# msgeq7-simple.net
KiCad netlist of a schematic drawn in EAGLE
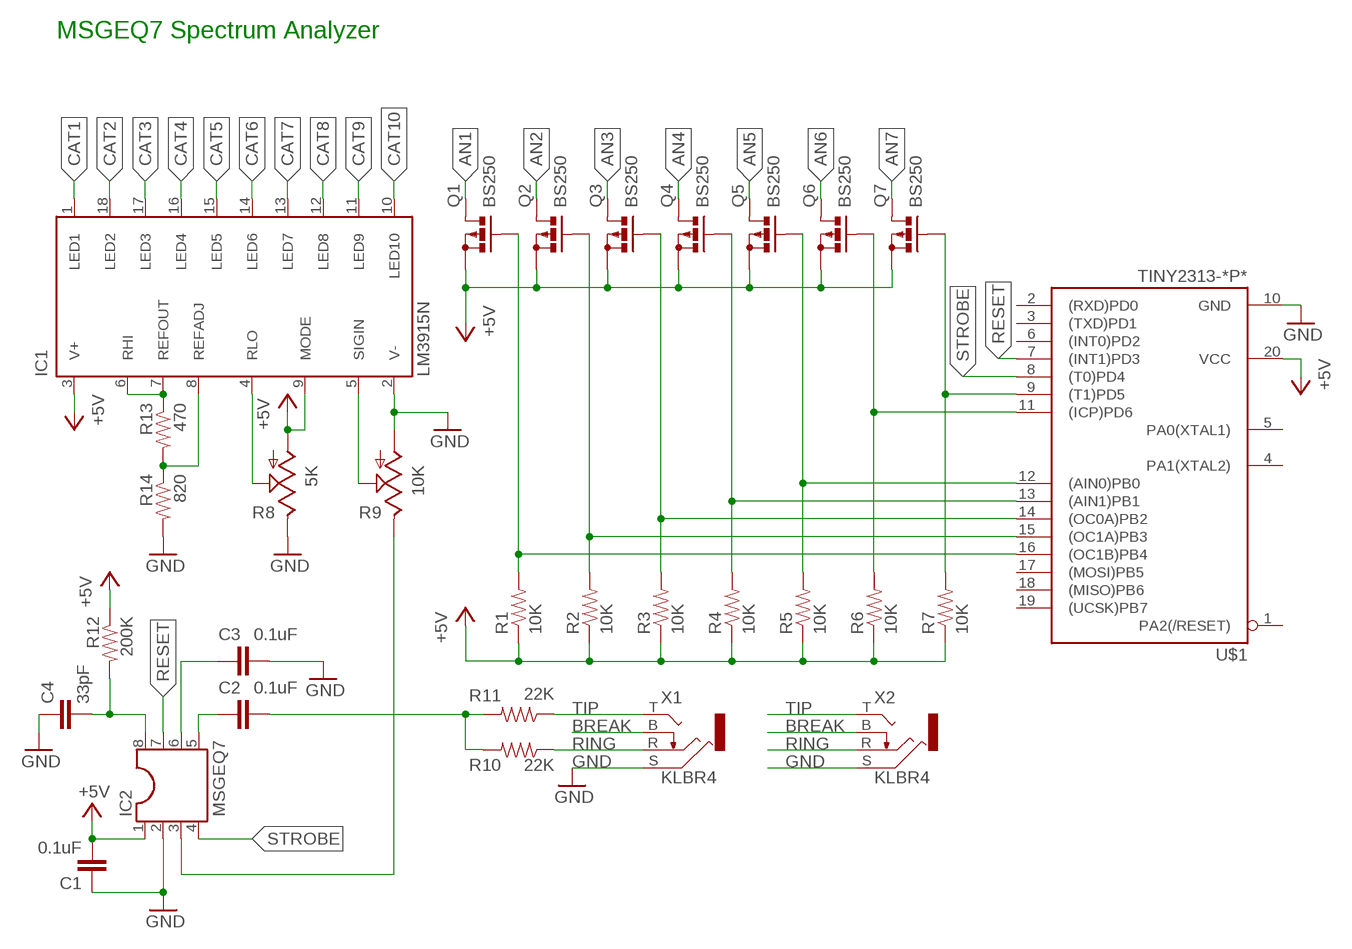
[diagram p0: schematic, sheet 1]

(export (version "E")
  (design (tool "Eeschema 10.0.6"))
  (components
    (comp (ref "C1")
      (value "0.1uF")
      (footprint "eagle-import:CAP-PTH-SMALL")
      (libsource (lib "eagle-import") (part "CAPPTH"))
    )
    (comp (ref "C2")
      (value "0.1uF")
      (footprint "eagle-import:CAP-PTH-SMALL")
      (libsource (lib "eagle-import") (part "CAPPTH"))
    )
    (comp (ref "C3")
      (value "0.1uF")
      (footprint "eagle-import:CAP-PTH-SMALL")
      (libsource (lib "eagle-import") (part "CAPPTH"))
    )
    (comp (ref "C4")
      (value "33pF")
      (footprint "eagle-import:CAP-PTH-SMALL")
      (libsource (lib "eagle-import") (part "CAPPTH"))
    )
    (comp (ref "IC1")
      (value "LM3915N")
      (footprint "eagle-import:DIL18")
      (libsource (lib "eagle-import") (part "LM391N5"))
    )
    (comp (ref "IC2")
      (value "MSGEQ7")
      (footprint "eagle-import:DIL08")
      (libsource (lib "eagle-import") (part "DIL8"))
    )
    (comp (ref "Q1")
      (value "BS250")
      (footprint "eagle-import:SOT54E")
      (libsource (lib "eagle-import") (part "BS250"))
    )
    (comp (ref "Q2")
      (value "BS250")
      (footprint "eagle-import:SOT54E")
      (libsource (lib "eagle-import") (part "BS250"))
    )
    (comp (ref "Q3")
      (value "BS250")
      (footprint "eagle-import:SOT54E")
      (libsource (lib "eagle-import") (part "BS250"))
    )
    (comp (ref "Q4")
      (value "BS250")
      (footprint "eagle-import:SOT54E")
      (libsource (lib "eagle-import") (part "BS250"))
    )
    (comp (ref "Q5")
      (value "BS250")
      (footprint "eagle-import:SOT54E")
      (libsource (lib "eagle-import") (part "BS250"))
    )
    (comp (ref "Q6")
      (value "BS250")
      (footprint "eagle-import:SOT54E")
      (libsource (lib "eagle-import") (part "BS250"))
    )
    (comp (ref "Q7")
      (value "BS250")
      (footprint "eagle-import:SOT54E")
      (libsource (lib "eagle-import") (part "BS250"))
    )
    (comp (ref "R1")
      (value "10K")
      (footprint "eagle-import:AXIAL-0.4")
      (libsource (lib "eagle-import") (part "RESISTORPTH-1/4W"))
    )
    (comp (ref "R2")
      (value "10K")
      (footprint "eagle-import:AXIAL-0.4")
      (libsource (lib "eagle-import") (part "RESISTORPTH-1/4W"))
    )
    (comp (ref "R3")
      (value "10K")
      (footprint "eagle-import:AXIAL-0.4")
      (libsource (lib "eagle-import") (part "RESISTORPTH-1/4W"))
    )
    (comp (ref "R4")
      (value "10K")
      (footprint "eagle-import:AXIAL-0.4")
      (libsource (lib "eagle-import") (part "RESISTORPTH-1/4W"))
    )
    (comp (ref "R5")
      (value "10K")
      (footprint "eagle-import:AXIAL-0.4")
      (libsource (lib "eagle-import") (part "RESISTORPTH-1/4W"))
    )
    (comp (ref "R6")
      (value "10K")
      (footprint "eagle-import:AXIAL-0.4")
      (libsource (lib "eagle-import") (part "RESISTORPTH-1/4W"))
    )
    (comp (ref "R7")
      (value "10K")
      (footprint "eagle-import:AXIAL-0.4")
      (libsource (lib "eagle-import") (part "RESISTORPTH-1/4W"))
    )
    (comp (ref "R8")
      (value "5K")
      (footprint "eagle-import:LI10")
      (libsource (lib "eagle-import") (part "TRIM_US-LI10"))
    )
    (comp (ref "R9")
      (value "10K")
      (footprint "eagle-import:LI10")
      (libsource (lib "eagle-import") (part "TRIM_US-LI10"))
    )
    (comp (ref "R10")
      (value "22K")
      (footprint "eagle-import:AXIAL-0.4")
      (libsource (lib "eagle-import") (part "RESISTORPTH-1/4W"))
    )
    (comp (ref "R11")
      (value "22K")
      (footprint "eagle-import:AXIAL-0.4")
      (libsource (lib "eagle-import") (part "RESISTORPTH-1/4W"))
    )
    (comp (ref "R12")
      (value "200K")
      (footprint "eagle-import:AXIAL-0.4")
      (libsource (lib "eagle-import") (part "RESISTORPTH-1/4W"))
    )
    (comp (ref "R13")
      (value "470")
      (footprint "eagle-import:AXIAL-0.4")
      (libsource (lib "eagle-import") (part "RESISTORPTH-1/4W"))
    )
    (comp (ref "R14")
      (value "820")
      (footprint "eagle-import:AXIAL-0.4")
      (libsource (lib "eagle-import") (part "RESISTORPTH-1/4W"))
    )
    (comp (ref "U$1")
      (value "TINY2313-*P*")
      (footprint "eagle-import:DIL20")
      (libsource (lib "eagle-import") (part "TINY2313-P"))
    )
    (comp (ref "X1")
      (value "KLBR4")
      (footprint "eagle-import:KLBR4")
      (libsource (lib "eagle-import") (part "KLBR4"))
    )
    (comp (ref "X2")
      (value "KLBR4")
      (footprint "eagle-import:KLBR4")
      (libsource (lib "eagle-import") (part "KLBR4"))
    )
  )
  (nets
    (net (code "1") (name "+5V") (class "Default")
      (node (ref "C1") (pin "2") (pinfunction "2_2") (pintype "passive"))
      (node (ref "IC1") (pin "3") (pinfunction "V+_3") (pintype "power_in"))
      (node (ref "IC1") (pin "9") (pinfunction "MODE_9") (pintype "input"))
      (node (ref "IC2") (pin "1") (pinfunction "1_1") (pintype "passive"))
      (node (ref "Q1") (pin "S") (pinfunction "S_S") (pintype "passive"))
      (node (ref "Q2") (pin "S") (pinfunction "S_S") (pintype "passive"))
      (node (ref "Q3") (pin "S") (pinfunction "S_S") (pintype "passive"))
      (node (ref "Q4") (pin "S") (pinfunction "S_S") (pintype "passive"))
      (node (ref "Q5") (pin "S") (pinfunction "S_S") (pintype "passive"))
      (node (ref "Q6") (pin "S") (pinfunction "S_S") (pintype "passive"))
      (node (ref "Q7") (pin "S") (pinfunction "S_S") (pintype "passive"))
      (node (ref "R1") (pin "P$1") (pinfunction "1_P$1") (pintype "passive"))
      (node (ref "R12") (pin "P$1") (pinfunction "1_P$1") (pintype "passive"))
      (node (ref "R2") (pin "P$1") (pinfunction "1_P$1") (pintype "passive"))
      (node (ref "R3") (pin "P$1") (pinfunction "1_P$1") (pintype "passive"))
      (node (ref "R4") (pin "P$1") (pinfunction "1_P$1") (pintype "passive"))
      (node (ref "R5") (pin "P$1") (pinfunction "1_P$1") (pintype "passive"))
      (node (ref "R6") (pin "P$1") (pinfunction "1_P$1") (pintype "passive"))
      (node (ref "R7") (pin "P$1") (pinfunction "1_P$1") (pintype "passive"))
      (node (ref "R8") (pin "A") (pinfunction "A_A") (pintype "passive"))
      (node (ref "U$1") (pin "20") (pinfunction "VCC_20") (pintype "power_in"))
    )
    (net (code "2") (name "/BREAK") (class "Default")
      (node (ref "X1") (pin "B") (pinfunction "B_B") (pintype "passive"))
      (node (ref "X2") (pin "B") (pinfunction "B_B") (pintype "passive"))
    )
    (net (code "3") (name "/RING") (class "Default")
      (node (ref "R10") (pin "P$1") (pinfunction "1_P$1") (pintype "passive"))
      (node (ref "X1") (pin "R") (pinfunction "R_R") (pintype "passive"))
      (node (ref "X2") (pin "R") (pinfunction "R_R") (pintype "passive"))
    )
    (net (code "4") (name "/TIP") (class "Default")
      (node (ref "R11") (pin "P$1") (pinfunction "1_P$1") (pintype "passive"))
      (node (ref "X1") (pin "T") (pinfunction "T_T") (pintype "passive"))
      (node (ref "X2") (pin "T") (pinfunction "T_T") (pintype "passive"))
    )
    (net (code "5") (name "AN1") (class "Default")
      (node (ref "Q1") (pin "D") (pinfunction "D_D") (pintype "passive"))
    )
    (net (code "6") (name "AN2") (class "Default")
      (node (ref "Q2") (pin "D") (pinfunction "D_D") (pintype "passive"))
    )
    (net (code "7") (name "AN3") (class "Default")
      (node (ref "Q3") (pin "D") (pinfunction "D_D") (pintype "passive"))
    )
    (net (code "8") (name "AN4") (class "Default")
      (node (ref "Q4") (pin "D") (pinfunction "D_D") (pintype "passive"))
    )
    (net (code "9") (name "AN5") (class "Default")
      (node (ref "Q5") (pin "D") (pinfunction "D_D") (pintype "passive"))
    )
    (net (code "10") (name "AN6") (class "Default")
      (node (ref "Q6") (pin "D") (pinfunction "D_D") (pintype "passive"))
    )
    (net (code "11") (name "AN7") (class "Default")
      (node (ref "Q7") (pin "D") (pinfunction "D_D") (pintype "passive"))
    )
    (net (code "12") (name "CAT1") (class "Default")
      (node (ref "IC1") (pin "1") (pinfunction "LED1_1") (pintype "output"))
    )
    (net (code "13") (name "CAT2") (class "Default")
      (node (ref "IC1") (pin "18") (pinfunction "LED2_18") (pintype "output"))
    )
    (net (code "14") (name "CAT3") (class "Default")
      (node (ref "IC1") (pin "17") (pinfunction "LED3_17") (pintype "output"))
    )
    (net (code "15") (name "CAT4") (class "Default")
      (node (ref "IC1") (pin "16") (pinfunction "LED4_16") (pintype "output"))
    )
    (net (code "16") (name "CAT5") (class "Default")
      (node (ref "IC1") (pin "15") (pinfunction "LED5_15") (pintype "output"))
    )
    (net (code "17") (name "CAT6") (class "Default")
      (node (ref "IC1") (pin "14") (pinfunction "LED6_14") (pintype "output"))
    )
    (net (code "18") (name "CAT7") (class "Default")
      (node (ref "IC1") (pin "13") (pinfunction "LED7_13") (pintype "output"))
    )
    (net (code "19") (name "CAT8") (class "Default")
      (node (ref "IC1") (pin "12") (pinfunction "LED8_12") (pintype "output"))
    )
    (net (code "20") (name "CAT9") (class "Default")
      (node (ref "IC1") (pin "11") (pinfunction "LED9_11") (pintype "output"))
    )
    (net (code "21") (name "CAT10") (class "Default")
      (node (ref "IC1") (pin "10") (pinfunction "LED10_10") (pintype "output"))
    )
    (net (code "22") (name "GND") (class "Default")
      (node (ref "C1") (pin "1") (pinfunction "1_1") (pintype "passive"))
      (node (ref "C3") (pin "1") (pinfunction "1_1") (pintype "passive"))
      (node (ref "C4") (pin "1") (pinfunction "1_1") (pintype "passive"))
      (node (ref "IC1") (pin "2") (pinfunction "V-_2") (pintype "power_in"))
      (node (ref "IC2") (pin "2") (pinfunction "2_2") (pintype "passive"))
      (node (ref "R14") (pin "P$2") (pinfunction "2_P$2") (pintype "passive"))
      (node (ref "R8") (pin "E") (pinfunction "E_E") (pintype "passive"))
      (node (ref "R9") (pin "A") (pinfunction "A_A") (pintype "passive"))
      (node (ref "U$1") (pin "10") (pinfunction "GND_10") (pintype "power_in"))
      (node (ref "X1") (pin "S") (pinfunction "S_S") (pintype "passive"))
      (node (ref "X2") (pin "S") (pinfunction "S_S") (pintype "passive"))
    )
    (net (code "23") (name "Net-(C2-Pad2)") (class "Default")
      (node (ref "C2") (pin "2") (pinfunction "2_2") (pintype "passive"))
      (node (ref "IC2") (pin "5") (pinfunction "5_5") (pintype "passive"))
    )
    (net (code "24") (name "Net-(C3-Pad2)") (class "Default")
      (node (ref "C3") (pin "2") (pinfunction "2_2") (pintype "passive"))
      (node (ref "IC2") (pin "6") (pinfunction "6_6") (pintype "passive"))
    )
    (net (code "25") (name "Net-(IC1-REFADJ)") (class "Default")
      (node (ref "IC1") (pin "8") (pinfunction "REFADJ_8") (pintype "passive"))
      (node (ref "R13") (pin "P$2") (pinfunction "2_P$2") (pintype "passive"))
      (node (ref "R14") (pin "P$1") (pinfunction "1_P$1") (pintype "passive"))
    )
    (net (code "26") (name "Net-(IC1-REFOUT)") (class "Default")
      (node (ref "IC1") (pin "6") (pinfunction "RHI_6") (pintype "input"))
      (node (ref "IC1") (pin "7") (pinfunction "REFOUT_7") (pintype "output"))
      (node (ref "R13") (pin "P$1") (pinfunction "1_P$1") (pintype "passive"))
    )
    (net (code "27") (name "Net-(IC1-RLO)") (class "Default")
      (node (ref "IC1") (pin "4") (pinfunction "RLO_4") (pintype "input"))
      (node (ref "R8") (pin "S") (pinfunction "S_S") (pintype "passive"))
    )
    (net (code "28") (name "Net-(IC1-SIGIN)") (class "Default")
      (node (ref "IC1") (pin "5") (pinfunction "SIGIN_5") (pintype "input"))
      (node (ref "R9") (pin "S") (pinfunction "S_S") (pintype "passive"))
    )
    (net (code "29") (name "Net-(IC2-Pad3)") (class "Default")
      (node (ref "IC2") (pin "3") (pinfunction "3_3") (pintype "passive"))
      (node (ref "R9") (pin "E") (pinfunction "E_E") (pintype "passive"))
    )
    (net (code "30") (name "Net-(R1-2)") (class "Default")
      (node (ref "Q1") (pin "G") (pinfunction "G_G") (pintype "passive"))
      (node (ref "R1") (pin "P$2") (pinfunction "2_P$2") (pintype "passive"))
      (node (ref "U$1") (pin "16") (pinfunction "(OC1B)PB4_16") (pintype "bidirectional"))
    )
    (net (code "31") (name "Net-(R2-2)") (class "Default")
      (node (ref "Q2") (pin "G") (pinfunction "G_G") (pintype "passive"))
      (node (ref "R2") (pin "P$2") (pinfunction "2_P$2") (pintype "passive"))
      (node (ref "U$1") (pin "15") (pinfunction "(OC1A)PB3_15") (pintype "bidirectional"))
    )
    (net (code "32") (name "Net-(R3-2)") (class "Default")
      (node (ref "Q3") (pin "G") (pinfunction "G_G") (pintype "passive"))
      (node (ref "R3") (pin "P$2") (pinfunction "2_P$2") (pintype "passive"))
      (node (ref "U$1") (pin "14") (pinfunction "(OC0A)PB2_14") (pintype "bidirectional"))
    )
    (net (code "33") (name "Net-(R4-2)") (class "Default")
      (node (ref "Q4") (pin "G") (pinfunction "G_G") (pintype "passive"))
      (node (ref "R4") (pin "P$2") (pinfunction "2_P$2") (pintype "passive"))
      (node (ref "U$1") (pin "13") (pinfunction "(AIN1)PB1_13") (pintype "bidirectional"))
    )
    (net (code "34") (name "Net-(R5-2)") (class "Default")
      (node (ref "Q5") (pin "G") (pinfunction "G_G") (pintype "passive"))
      (node (ref "R5") (pin "P$2") (pinfunction "2_P$2") (pintype "passive"))
      (node (ref "U$1") (pin "12") (pinfunction "(AIN0)PB0_12") (pintype "bidirectional"))
    )
    (net (code "35") (name "Net-(R6-2)") (class "Default")
      (node (ref "Q6") (pin "G") (pinfunction "G_G") (pintype "passive"))
      (node (ref "R6") (pin "P$2") (pinfunction "2_P$2") (pintype "passive"))
      (node (ref "U$1") (pin "11") (pinfunction "(ICP)PD6_11") (pintype "bidirectional"))
    )
    (net (code "36") (name "Net-(R7-2)") (class "Default")
      (node (ref "Q7") (pin "G") (pinfunction "G_G") (pintype "passive"))
      (node (ref "R7") (pin "P$2") (pinfunction "2_P$2") (pintype "passive"))
      (node (ref "U$1") (pin "9") (pinfunction "(T1)PD5_9") (pintype "bidirectional"))
    )
    (net (code "37") (name "Net-(R10-2)") (class "Default")
      (node (ref "C2") (pin "1") (pinfunction "1_1") (pintype "passive"))
      (node (ref "R10") (pin "P$2") (pinfunction "2_P$2") (pintype "passive"))
      (node (ref "R11") (pin "P$2") (pinfunction "2_P$2") (pintype "passive"))
    )
    (net (code "38") (name "Net-(R12-2)") (class "Default")
      (node (ref "C4") (pin "2") (pinfunction "2_2") (pintype "passive"))
      (node (ref "IC2") (pin "8") (pinfunction "8_8") (pintype "passive"))
      (node (ref "R12") (pin "P$2") (pinfunction "2_P$2") (pintype "passive"))
    )
    (net (code "39") (name "RESET") (class "Default")
      (node (ref "IC2") (pin "7") (pinfunction "7_7") (pintype "passive"))
      (node (ref "U$1") (pin "7") (pinfunction "(INT1)PD3_7") (pintype "bidirectional"))
    )
    (net (code "40") (name "STROBE") (class "Default")
      (node (ref "IC2") (pin "4") (pinfunction "4_4") (pintype "passive"))
      (node (ref "U$1") (pin "8") (pinfunction "(T0)PD4_8") (pintype "bidirectional"))
    )
    (net (code "41") (name "unconnected-(U$1-(INT0)PD2-Pad6)") (class "Default")
      (node (ref "U$1") (pin "6") (pinfunction "(INT0)PD2_6") (pintype "bidirectional"))
    )
    (net (code "42") (name "unconnected-(U$1-(MISO)PB6-Pad18)") (class "Default")
      (node (ref "U$1") (pin "18") (pinfunction "(MISO)PB6_18") (pintype "bidirectional"))
    )
    (net (code "43") (name "unconnected-(U$1-(MOSI)PB5-Pad17)") (class "Default")
      (node (ref "U$1") (pin "17") (pinfunction "(MOSI)PB5_17") (pintype "bidirectional"))
    )
    (net (code "44") (name "unconnected-(U$1-(RXD)PD0-Pad2)") (class "Default")
      (node (ref "U$1") (pin "2") (pinfunction "(RXD)PD0_2") (pintype "bidirectional"))
    )
    (net (code "45") (name "unconnected-(U$1-(TXD)PD1-Pad3)") (class "Default")
      (node (ref "U$1") (pin "3") (pinfunction "(TXD)PD1_3") (pintype "bidirectional"))
    )
    (net (code "46") (name "unconnected-(U$1-(UCSK)PB7-Pad19)") (class "Default")
      (node (ref "U$1") (pin "19") (pinfunction "(UCSK)PB7_19") (pintype "bidirectional"))
    )
    (net (code "47") (name "unconnected-(U$1-PA0(XTAL1)-Pad5)") (class "Default")
      (node (ref "U$1") (pin "5") (pinfunction "PA0(XTAL1)_5") (pintype "bidirectional"))
    )
    (net (code "48") (name "unconnected-(U$1-PA1(XTAL2)-Pad4)") (class "Default")
      (node (ref "U$1") (pin "4") (pinfunction "PA1(XTAL2)_4") (pintype "bidirectional"))
    )
    (net (code "49") (name "unconnected-(U$1-PA2({slash}RESET)-Pad1)") (class "Default")
      (node (ref "U$1") (pin "1") (pinfunction "PA2(/RESET)_1") (pintype "input"))
    )
  )
)
